# Arduino_Mini.net
KiCad netlist of a schematic drawn in EAGLE
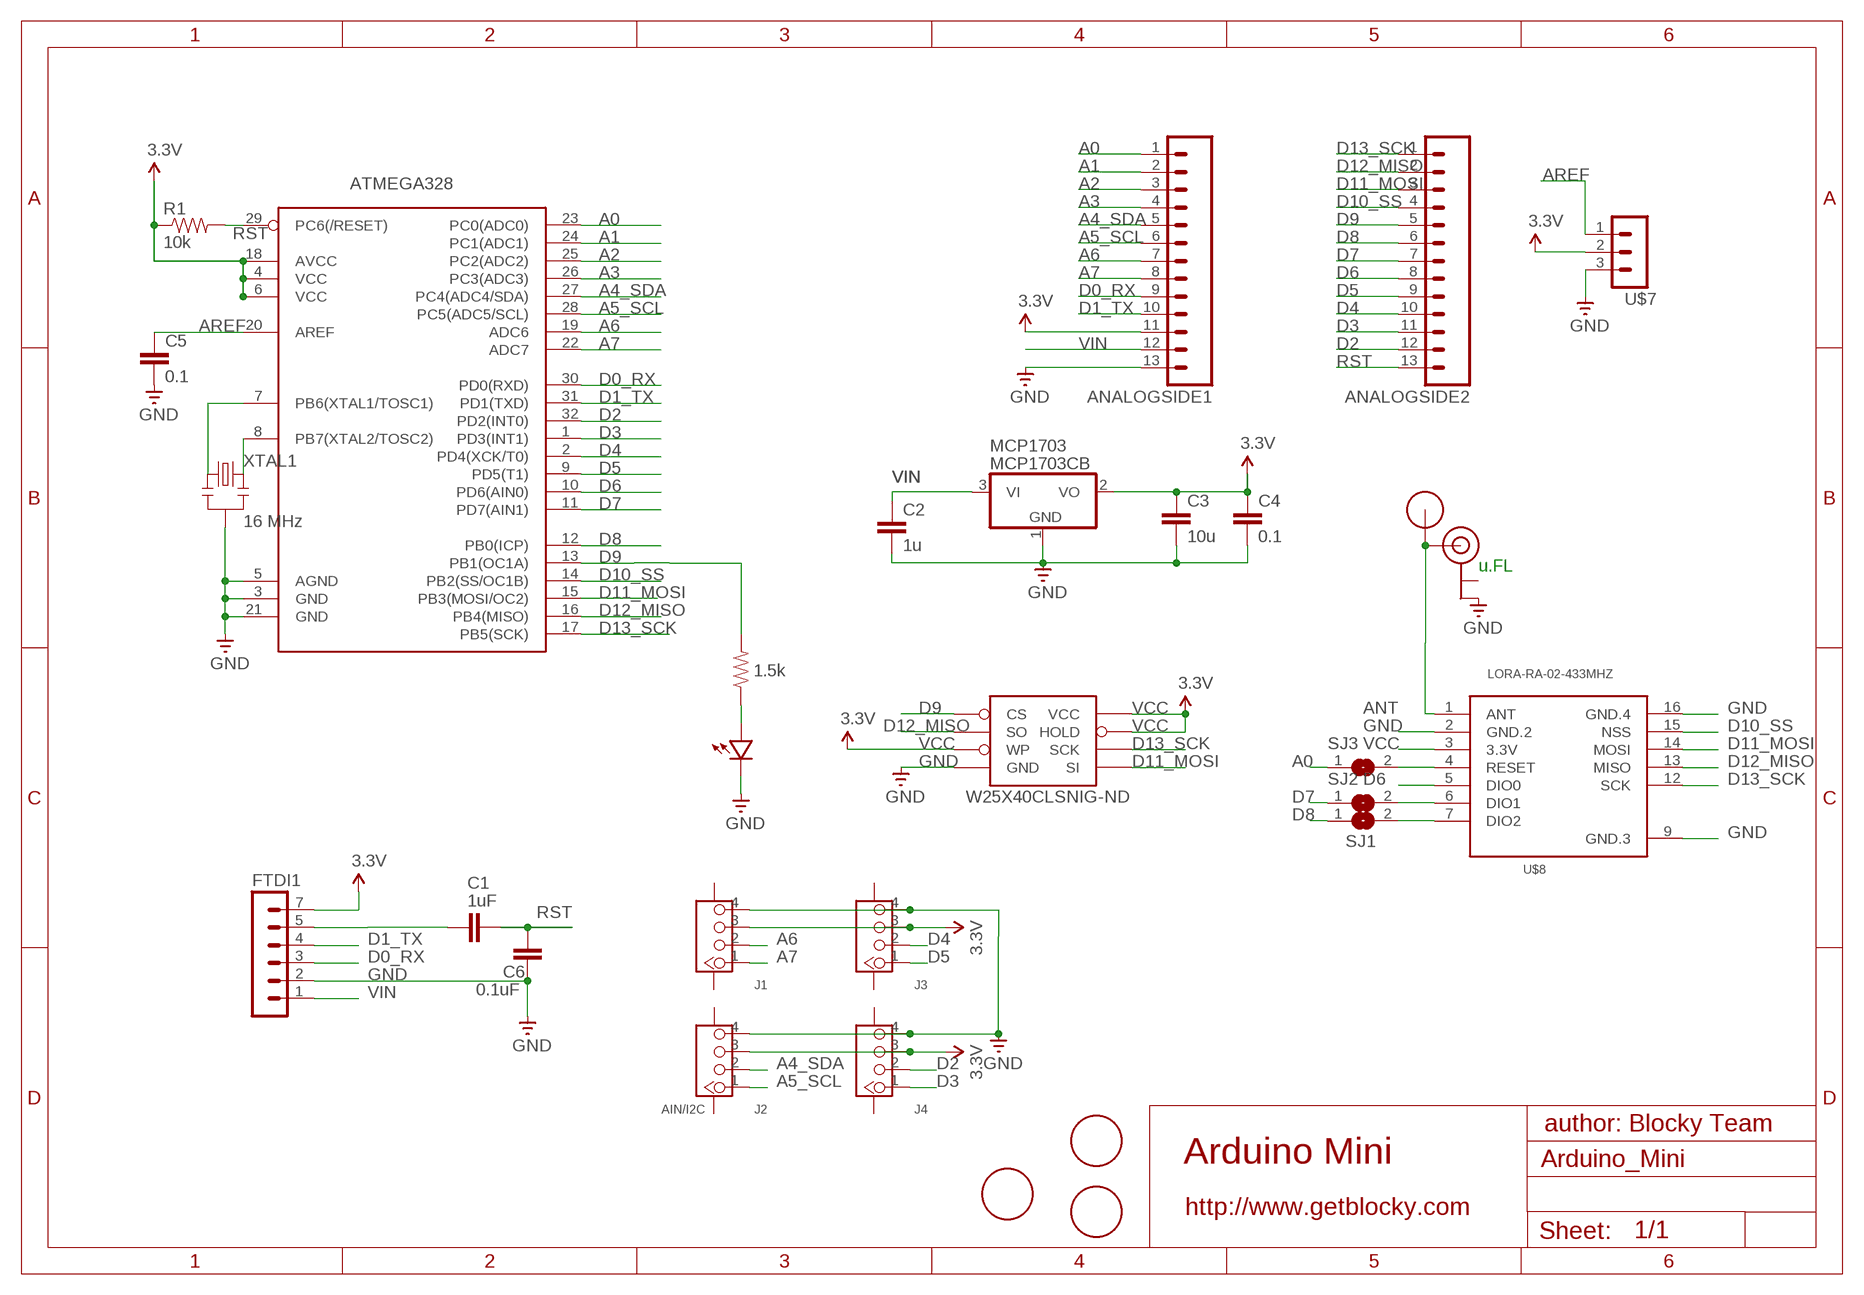
[diagram p0: schematic, sheet 1]

(export (version "E")
  (design (tool "Eeschema 10.0.6"))
  (components
    (comp (ref "ANALOGSIDE1")
      (value "HDR_13PINTHIN_RINGS")
      (footprint "eagle-import:1X13_THINRINGS")
      (libsource (lib "eagle-import") (part "HDR_13PINTHIN_RINGS"))
    )
    (comp (ref "ANALOGSIDE2")
      (value "HDR_13PINTHIN_RINGS")
      (footprint "eagle-import:1X13_THINRINGS")
      (libsource (lib "eagle-import") (part "HDR_13PINTHIN_RINGS"))
    )
    (comp (ref "ATMEGA328")
      (value "ATMega-328")
      (footprint "eagle-import:TQFP32-08")
      (libsource (lib "eagle-import") (part "ATMEGA168/328TQFP32"))
    )
    (comp (ref "C1")
      (value "1uF")
      (footprint "eagle-import:0603-CAP")
      (libsource (lib "eagle-import") (part "CAP0603-CAP"))
    )
    (comp (ref "C2")
      (value "1u")
      (footprint "eagle-import:0603-CAP")
      (libsource (lib "eagle-import") (part "CAP0603-CAP"))
    )
    (comp (ref "C3")
      (value "10u")
      (footprint "eagle-import:0805-CAP")
      (libsource (lib "eagle-import") (part "CAP0805-CAP"))
    )
    (comp (ref "C4")
      (value "0.1")
      (footprint "eagle-import:0603-CAP")
      (libsource (lib "eagle-import") (part "CAP0603-CAP"))
    )
    (comp (ref "C5")
      (value "0.1")
      (footprint "eagle-import:0603-CAP")
      (libsource (lib "eagle-import") (part "CAP0603-CAP"))
    )
    (comp (ref "C6")
      (value "0.1uF")
      (footprint "eagle-import:0603-CAP")
      (libsource (lib "eagle-import") (part "CAP0603-CAP"))
    )
    (comp (ref "FTDI1")
      (value "HDR_6PINTHINRINGS")
      (footprint "eagle-import:1X06_NS_THINRINGS")
      (libsource (lib "eagle-import") (part "HDR_6PINTHINRINGS"))
    )
    (comp (ref "J1")
      (value "4P-SMD-2.0-90D")
      (footprint "eagle-import:HW4-SMD-2.0-90D")
      (libsource (lib "eagle-import") (part "GROVE-CONNECTOR-SMD-90D(4+2P-2.0)"))
    )
    (comp (ref "J2")
      (value "AIN/I2C")
      (footprint "eagle-import:HW4-SMD-2.0-90D")
      (libsource (lib "eagle-import") (part "GROVE-CONNECTOR-SMD-90D(4+2P-2.0)"))
    )
    (comp (ref "J3")
      (value "4P-SMD-2.0-90D")
      (footprint "eagle-import:HW4-SMD-2.0-90D")
      (libsource (lib "eagle-import") (part "GROVE-CONNECTOR-SMD-90D(4+2P-2.0)"))
    )
    (comp (ref "J4")
      (value "4P-SMD-2.0-90D")
      (footprint "eagle-import:HW4-SMD-2.0-90D")
      (libsource (lib "eagle-import") (part "GROVE-CONNECTOR-SMD-90D(4+2P-2.0)"))
    )
    (comp (ref "LED")
      (value "LED0603")
      (footprint "eagle-import:0603-LED")
      (libsource (lib "eagle-import") (part "LED0603"))
    )
    (comp (ref "MCP1703")
      (value "MCP1703CB")
      (footprint "eagle-import:SOT23")
      (libsource (lib "eagle-import") (part "MCP1703CB"))
    )
    (comp (ref "R1")
      (value "10k")
      (footprint "eagle-import:0603-RES")
      (libsource (lib "eagle-import") (part "RESISTOR0603-RES"))
    )
    (comp (ref "R2")
      (value "1.5k")
      (footprint "eagle-import:0603-RES")
      (libsource (lib "eagle-import") (part "RESISTOR0603-RES"))
    )
    (comp (ref "SJ1")
      (value "SOLDERJUMPERREFLOW")
      (footprint "eagle-import:SOLDERJUMPER_REFLOW")
      (libsource (lib "eagle-import") (part "SOLDERJUMPERREFLOW"))
    )
    (comp (ref "SJ2")
      (value "SOLDERJUMPERREFLOW")
      (footprint "eagle-import:SOLDERJUMPER_REFLOW")
      (libsource (lib "eagle-import") (part "SOLDERJUMPERREFLOW"))
    )
    (comp (ref "SJ3")
      (value "SOLDERJUMPERREFLOW")
      (footprint "eagle-import:SOLDERJUMPER_REFLOW")
      (libsource (lib "eagle-import") (part "SOLDERJUMPERREFLOW"))
    )
    (comp (ref "U$1")
      (value "RFM12B_ANTENNA\"\"")
      (footprint "eagle-import:RFM12B-ANTENNA")
      (libsource (lib "eagle-import") (part "RFM12B_ANTENNA{dblquote}{dblquote}"))
    )
    (comp (ref "U$2")
      (value "FIDUCIAL1.5MM")
      (footprint "eagle-import:FIDUCIAL_1.5MM")
      (libsource (lib "eagle-import") (part "FIDUCIAL1.5MM"))
    )
    (comp (ref "U$4")
      (value "U.FL")
      (footprint "eagle-import:U.FL")
      (libsource (lib "eagle-import") (part "U.FL"))
    )
    (comp (ref "U$5")
      (value "FIDUCIAL1.5MM")
      (footprint "eagle-import:FIDUCIAL_1.5MM")
      (libsource (lib "eagle-import") (part "FIDUCIAL1.5MM"))
    )
    (comp (ref "U$6")
      (value "FIDUCIAL1.5MM")
      (footprint "eagle-import:FIDUCIAL_1.5MM")
      (libsource (lib "eagle-import") (part "FIDUCIAL1.5MM"))
    )
    (comp (ref "U$7")
      (value "HDR_3PINTHINRINGS")
      (footprint "eagle-import:1X03_NS_THINRINGS")
      (libsource (lib "eagle-import") (part "HDR_3PINTHINRINGS"))
    )
    (comp (ref "U$8")
      (value "LORA-RA-02-433MHZ")
      (footprint "eagle-import:LORA-RA2-SMD")
      (libsource (lib "eagle-import") (part "LORA-RA-02-433MHZ"))
    )
    (comp (ref "W25X40CLSNIG-ND")
      (value "AT25F512BJEDEC_3.9MM")
      (footprint "eagle-import:SO08")
      (libsource (lib "eagle-import") (part "AT25F512BJEDEC_3.9MM"))
    )
    (comp (ref "XTAL1")
      (value "16 MHz")
      (footprint "eagle-import:RESONATOR-SMD")
      (libsource (lib "eagle-import") (part "RESONATORSMD"))
    )
  )
  (nets
    (net (code "1") (name "/A0") (class "Default")
      (node (ref "ANALOGSIDE1") (pin "1") (pinfunction "1_1") (pintype "passive"))
      (node (ref "ATMEGA328") (pin "23") (pinfunction "PC0(ADC0)_23") (pintype "bidirectional"))
      (node (ref "SJ3") (pin "1") (pinfunction "1_1") (pintype "passive"))
    )
    (net (code "2") (name "/A1") (class "Default")
      (node (ref "ANALOGSIDE1") (pin "2") (pinfunction "2_2") (pintype "passive"))
      (node (ref "ATMEGA328") (pin "24") (pinfunction "PC1(ADC1)_24") (pintype "bidirectional"))
    )
    (net (code "3") (name "/A2") (class "Default")
      (node (ref "ANALOGSIDE1") (pin "3") (pinfunction "3_3") (pintype "passive"))
      (node (ref "ATMEGA328") (pin "25") (pinfunction "PC2(ADC2)_25") (pintype "bidirectional"))
    )
    (net (code "4") (name "/A3") (class "Default")
      (node (ref "ANALOGSIDE1") (pin "4") (pinfunction "4_4") (pintype "passive"))
      (node (ref "ATMEGA328") (pin "26") (pinfunction "PC3(ADC3)_26") (pintype "bidirectional"))
    )
    (net (code "5") (name "/A4_SDA") (class "Default")
      (node (ref "ANALOGSIDE1") (pin "5") (pinfunction "5_5") (pintype "passive"))
      (node (ref "ATMEGA328") (pin "27") (pinfunction "PC4(ADC4/SDA)_27") (pintype "bidirectional"))
      (node (ref "J2") (pin "2") (pinfunction "2_2") (pintype "bidirectional"))
    )
    (net (code "6") (name "/A5_SCL") (class "Default")
      (node (ref "ANALOGSIDE1") (pin "6") (pinfunction "6_6") (pintype "passive"))
      (node (ref "ATMEGA328") (pin "28") (pinfunction "PC5(ADC5/SCL)_28") (pintype "bidirectional"))
      (node (ref "J2") (pin "1") (pinfunction "1_1") (pintype "bidirectional"))
    )
    (net (code "7") (name "/A6") (class "Default")
      (node (ref "ANALOGSIDE1") (pin "7") (pinfunction "7_7") (pintype "passive"))
      (node (ref "ATMEGA328") (pin "19") (pinfunction "ADC6_19") (pintype "bidirectional"))
      (node (ref "J1") (pin "2") (pinfunction "2_2") (pintype "bidirectional"))
    )
    (net (code "8") (name "/A7") (class "Default")
      (node (ref "ANALOGSIDE1") (pin "8") (pinfunction "8_8") (pintype "passive"))
      (node (ref "ATMEGA328") (pin "22") (pinfunction "ADC7_22") (pintype "bidirectional"))
      (node (ref "J1") (pin "1") (pinfunction "1_1") (pintype "bidirectional"))
    )
    (net (code "9") (name "/ANT") (class "Default")
      (node (ref "U$1") (pin "P$1") (pinfunction "1_P$1") (pintype "bidirectional"))
      (node (ref "U$4") (pin "SIGNAL") (pinfunction "SIGNAL_SIGNAL") (pintype "bidirectional"))
      (node (ref "U$8") (pin "1") (pinfunction "ANT_1") (pintype "bidirectional"))
    )
    (net (code "10") (name "/AREF") (class "Default")
      (node (ref "ATMEGA328") (pin "20") (pinfunction "AREF_20") (pintype "bidirectional"))
      (node (ref "C5") (pin "1") (pinfunction "1_1") (pintype "passive"))
      (node (ref "U$7") (pin "1") (pinfunction "1_1") (pintype "passive"))
    )
    (net (code "11") (name "/D0_RX") (class "Default")
      (node (ref "ANALOGSIDE1") (pin "9") (pinfunction "9_9") (pintype "passive"))
      (node (ref "ATMEGA328") (pin "30") (pinfunction "PD0(RXD)_30") (pintype "bidirectional"))
      (node (ref "FTDI1") (pin "3") (pinfunction "3_3") (pintype "passive"))
    )
    (net (code "12") (name "/D1_TX") (class "Default")
      (node (ref "ANALOGSIDE1") (pin "10") (pinfunction "10_10") (pintype "passive"))
      (node (ref "ATMEGA328") (pin "31") (pinfunction "PD1(TXD)_31") (pintype "bidirectional"))
      (node (ref "FTDI1") (pin "4") (pinfunction "4_4") (pintype "passive"))
    )
    (net (code "13") (name "/D2") (class "Default")
      (node (ref "ANALOGSIDE2") (pin "12") (pinfunction "12_12") (pintype "passive"))
      (node (ref "ATMEGA328") (pin "32") (pinfunction "PD2(INT0)_32") (pintype "bidirectional"))
      (node (ref "J4") (pin "2") (pinfunction "2_2") (pintype "bidirectional"))
    )
    (net (code "14") (name "/D3") (class "Default")
      (node (ref "ANALOGSIDE2") (pin "11") (pinfunction "11_11") (pintype "passive"))
      (node (ref "ATMEGA328") (pin "1") (pinfunction "PD3(INT1)_1") (pintype "bidirectional"))
      (node (ref "J4") (pin "1") (pinfunction "1_1") (pintype "bidirectional"))
    )
    (net (code "15") (name "/D4") (class "Default")
      (node (ref "ANALOGSIDE2") (pin "10") (pinfunction "10_10") (pintype "passive"))
      (node (ref "ATMEGA328") (pin "2") (pinfunction "PD4(XCK/T0)_2") (pintype "bidirectional"))
      (node (ref "J3") (pin "2") (pinfunction "2_2") (pintype "bidirectional"))
    )
    (net (code "16") (name "/D5") (class "Default")
      (node (ref "ANALOGSIDE2") (pin "9") (pinfunction "9_9") (pintype "passive"))
      (node (ref "ATMEGA328") (pin "9") (pinfunction "PD5(T1)_9") (pintype "bidirectional"))
      (node (ref "J3") (pin "1") (pinfunction "1_1") (pintype "bidirectional"))
    )
    (net (code "17") (name "/D6") (class "Default")
      (node (ref "ANALOGSIDE2") (pin "8") (pinfunction "8_8") (pintype "passive"))
      (node (ref "ATMEGA328") (pin "10") (pinfunction "PD6(AIN0)_10") (pintype "bidirectional"))
      (node (ref "U$8") (pin "5") (pinfunction "DIO0_5") (pintype "bidirectional"))
    )
    (net (code "18") (name "/D7") (class "Default")
      (node (ref "ANALOGSIDE2") (pin "7") (pinfunction "7_7") (pintype "passive"))
      (node (ref "ATMEGA328") (pin "11") (pinfunction "PD7(AIN1)_11") (pintype "bidirectional"))
      (node (ref "SJ2") (pin "1") (pinfunction "1_1") (pintype "passive"))
    )
    (net (code "19") (name "/D8") (class "Default")
      (node (ref "ANALOGSIDE2") (pin "6") (pinfunction "6_6") (pintype "passive"))
      (node (ref "ATMEGA328") (pin "12") (pinfunction "PB0(ICP)_12") (pintype "bidirectional"))
      (node (ref "SJ1") (pin "1") (pinfunction "1_1") (pintype "passive"))
    )
    (net (code "20") (name "/D9") (class "Default")
      (node (ref "ANALOGSIDE2") (pin "5") (pinfunction "5_5") (pintype "passive"))
      (node (ref "ATMEGA328") (pin "13") (pinfunction "PB1(OC1A)_13") (pintype "bidirectional"))
      (node (ref "R2") (pin "2") (pinfunction "2_2") (pintype "passive"))
      (node (ref "W25X40CLSNIG-ND") (pin "1_CS") (pinfunction "CS_1_CS") (pintype "bidirectional"))
    )
    (net (code "21") (name "/D10_SS") (class "Default")
      (node (ref "ANALOGSIDE2") (pin "4") (pinfunction "4_4") (pintype "passive"))
      (node (ref "ATMEGA328") (pin "14") (pinfunction "PB2(SS/OC1B)_14") (pintype "bidirectional"))
      (node (ref "U$8") (pin "15") (pinfunction "NSS_15") (pintype "bidirectional"))
    )
    (net (code "22") (name "/D11_MOSI") (class "Default")
      (node (ref "ANALOGSIDE2") (pin "3") (pinfunction "3_3") (pintype "passive"))
      (node (ref "ATMEGA328") (pin "15") (pinfunction "PB3(MOSI/OC2)_15") (pintype "bidirectional"))
      (node (ref "U$8") (pin "14") (pinfunction "MOSI_14") (pintype "bidirectional"))
      (node (ref "W25X40CLSNIG-ND") (pin "5_SI") (pinfunction "SI_5_SI") (pintype "bidirectional"))
    )
    (net (code "23") (name "/D12_MISO") (class "Default")
      (node (ref "ANALOGSIDE2") (pin "2") (pinfunction "2_2") (pintype "passive"))
      (node (ref "ATMEGA328") (pin "16") (pinfunction "PB4(MISO)_16") (pintype "bidirectional"))
      (node (ref "U$8") (pin "13") (pinfunction "MISO_13") (pintype "bidirectional"))
      (node (ref "W25X40CLSNIG-ND") (pin "2_SO") (pinfunction "SO_2_SO") (pintype "bidirectional"))
    )
    (net (code "24") (name "/D13_SCK") (class "Default")
      (node (ref "ANALOGSIDE2") (pin "1") (pinfunction "1_1") (pintype "passive"))
      (node (ref "ATMEGA328") (pin "17") (pinfunction "PB5(SCK)_17") (pintype "bidirectional"))
      (node (ref "U$8") (pin "12") (pinfunction "SCK_12") (pintype "bidirectional"))
      (node (ref "W25X40CLSNIG-ND") (pin "6_SCK") (pinfunction "SCK_6_SCK") (pintype "bidirectional"))
    )
    (net (code "25") (name "/RST") (class "Default")
      (node (ref "ANALOGSIDE2") (pin "13") (pinfunction "13_13") (pintype "passive"))
      (node (ref "ATMEGA328") (pin "29") (pinfunction "PC6(/RESET)_29") (pintype "bidirectional"))
      (node (ref "C1") (pin "1") (pinfunction "1_1") (pintype "passive"))
      (node (ref "C6") (pin "1") (pinfunction "1_1") (pintype "passive"))
      (node (ref "R1") (pin "2") (pinfunction "2_2") (pintype "passive"))
    )
    (net (code "26") (name "/VIN") (class "Default")
      (node (ref "ANALOGSIDE1") (pin "12") (pinfunction "12_12") (pintype "passive"))
      (node (ref "C2") (pin "1") (pinfunction "1_1") (pintype "passive"))
      (node (ref "FTDI1") (pin "1") (pinfunction "1_1") (pintype "passive"))
      (node (ref "MCP1703") (pin "3") (pinfunction "VI_3") (pintype "input"))
    )
    (net (code "27") (name "3.3V") (class "Default")
      (node (ref "ANALOGSIDE1") (pin "11") (pinfunction "11_11") (pintype "passive"))
      (node (ref "ATMEGA328") (pin "18") (pinfunction "AVCC_18") (pintype "bidirectional"))
      (node (ref "ATMEGA328") (pin "4") (pinfunction "VCC_4") (pintype "bidirectional"))
      (node (ref "ATMEGA328") (pin "6") (pinfunction "VCC_6") (pintype "bidirectional"))
      (node (ref "C3") (pin "1") (pinfunction "1_1") (pintype "passive"))
      (node (ref "C4") (pin "1") (pinfunction "1_1") (pintype "passive"))
      (node (ref "FTDI1") (pin "7") (pinfunction "6_7") (pintype "passive"))
      (node (ref "J1") (pin "3") (pinfunction "3_3") (pintype "bidirectional"))
      (node (ref "J2") (pin "3") (pinfunction "3_3") (pintype "bidirectional"))
      (node (ref "J3") (pin "3") (pinfunction "3_3") (pintype "bidirectional"))
      (node (ref "J4") (pin "3") (pinfunction "3_3") (pintype "bidirectional"))
      (node (ref "MCP1703") (pin "2") (pinfunction "VO_2") (pintype "passive"))
      (node (ref "R1") (pin "1") (pinfunction "1_1") (pintype "passive"))
      (node (ref "U$7") (pin "2") (pinfunction "2_2") (pintype "passive"))
      (node (ref "U$8") (pin "3") (pinfunction "3.3V_3") (pintype "power_in"))
      (node (ref "W25X40CLSNIG-ND") (pin "3_WP") (pinfunction "WP_3_WP") (pintype "bidirectional"))
      (node (ref "W25X40CLSNIG-ND") (pin "7_HOLD") (pinfunction "HOLD_7_HOLD") (pintype "bidirectional"))
      (node (ref "W25X40CLSNIG-ND") (pin "8_VCC") (pinfunction "VCC_8_VCC") (pintype "bidirectional"))
    )
    (net (code "28") (name "GND") (class "Default")
      (node (ref "ANALOGSIDE1") (pin "13") (pinfunction "13_13") (pintype "passive"))
      (node (ref "ATMEGA328") (pin "21") (pinfunction "GND_21") (pintype "bidirectional"))
      (node (ref "ATMEGA328") (pin "3") (pinfunction "GND_3") (pintype "bidirectional"))
      (node (ref "ATMEGA328") (pin "5") (pinfunction "AGND_5") (pintype "bidirectional"))
      (node (ref "C2") (pin "2") (pinfunction "2_2") (pintype "passive"))
      (node (ref "C3") (pin "2") (pinfunction "2_2") (pintype "passive"))
      (node (ref "C4") (pin "2") (pinfunction "2_2") (pintype "passive"))
      (node (ref "C5") (pin "2") (pinfunction "2_2") (pintype "passive"))
      (node (ref "C6") (pin "2") (pinfunction "2_2") (pintype "passive"))
      (node (ref "FTDI1") (pin "2") (pinfunction "2_2") (pintype "passive"))
      (node (ref "J1") (pin "4") (pinfunction "4_4") (pintype "bidirectional"))
      (node (ref "J2") (pin "4") (pinfunction "4_4") (pintype "bidirectional"))
      (node (ref "J3") (pin "4") (pinfunction "4_4") (pintype "bidirectional"))
      (node (ref "J4") (pin "4") (pinfunction "4_4") (pintype "bidirectional"))
      (node (ref "LED") (pin "MINUS") (pinfunction "MINUS_MINUS") (pintype "passive"))
      (node (ref "MCP1703") (pin "1") (pinfunction "GND_1") (pintype "passive"))
      (node (ref "U$4") (pin "GND2") (pinfunction "GND_GND2") (pintype "bidirectional"))
      (node (ref "U$7") (pin "3") (pinfunction "3_3") (pintype "passive"))
      (node (ref "U$8") (pin "16") (pinfunction "GND.4_16") (pintype "power_in"))
      (node (ref "U$8") (pin "2") (pinfunction "GND.2_2") (pintype "power_in"))
      (node (ref "U$8") (pin "9") (pinfunction "GND.3_9") (pintype "power_in"))
      (node (ref "W25X40CLSNIG-ND") (pin "4_GND") (pinfunction "GND_4_GND") (pintype "bidirectional"))
      (node (ref "XTAL1") (pin "2") (pinfunction "2_2") (pintype "passive"))
    )
    (net (code "29") (name "Net-(ATMEGA328-PB6(XTAL1{slash}TOSC1))") (class "Default")
      (node (ref "ATMEGA328") (pin "7") (pinfunction "PB6(XTAL1/TOSC1)_7") (pintype "bidirectional"))
      (node (ref "XTAL1") (pin "1") (pinfunction "1_1") (pintype "passive"))
    )
    (net (code "30") (name "Net-(ATMEGA328-PB7(XTAL2{slash}TOSC2))") (class "Default")
      (node (ref "ATMEGA328") (pin "8") (pinfunction "PB7(XTAL2/TOSC2)_8") (pintype "bidirectional"))
      (node (ref "XTAL1") (pin "3") (pinfunction "3_3") (pintype "passive"))
    )
    (net (code "31") (name "Net-(C1-Pad2)") (class "Default")
      (node (ref "C1") (pin "2") (pinfunction "2_2") (pintype "passive"))
      (node (ref "FTDI1") (pin "5") (pinfunction "5_5") (pintype "passive"))
    )
    (net (code "32") (name "Net-(LED-PadPLUS)") (class "Default")
      (node (ref "LED") (pin "PLUS") (pinfunction "PLUS_PLUS") (pintype "passive"))
      (node (ref "R2") (pin "1") (pinfunction "1_1") (pintype "passive"))
    )
    (net (code "33") (name "Net-(U$8-DIO1)") (class "Default")
      (node (ref "SJ2") (pin "2") (pinfunction "2_2") (pintype "passive"))
      (node (ref "U$8") (pin "6") (pinfunction "DIO1_6") (pintype "bidirectional"))
    )
    (net (code "34") (name "Net-(U$8-DIO2)") (class "Default")
      (node (ref "SJ1") (pin "2") (pinfunction "2_2") (pintype "passive"))
      (node (ref "U$8") (pin "7") (pinfunction "DIO2_7") (pintype "bidirectional"))
    )
    (net (code "35") (name "Net-(U$8-RESET)") (class "Default")
      (node (ref "SJ3") (pin "2") (pinfunction "2_2") (pintype "passive"))
      (node (ref "U$8") (pin "4") (pinfunction "RESET_4") (pintype "bidirectional"))
    )
    (net (code "36") (name "unconnected-(J1-PadSS1)") (class "Default")
      (node (ref "J1") (pin "SS1") (pinfunction "SS1_SS1") (pintype "bidirectional"))
    )
    (net (code "37") (name "unconnected-(J1-PadSS2)") (class "Default")
      (node (ref "J1") (pin "SS2") (pinfunction "SS2_SS2") (pintype "bidirectional"))
    )
    (net (code "38") (name "unconnected-(J2-PadSS1)") (class "Default")
      (node (ref "J2") (pin "SS1") (pinfunction "SS1_SS1") (pintype "bidirectional"))
    )
    (net (code "39") (name "unconnected-(J2-PadSS2)") (class "Default")
      (node (ref "J2") (pin "SS2") (pinfunction "SS2_SS2") (pintype "bidirectional"))
    )
    (net (code "40") (name "unconnected-(J3-PadSS1)") (class "Default")
      (node (ref "J3") (pin "SS1") (pinfunction "SS1_SS1") (pintype "bidirectional"))
    )
    (net (code "41") (name "unconnected-(J3-PadSS2)") (class "Default")
      (node (ref "J3") (pin "SS2") (pinfunction "SS2_SS2") (pintype "bidirectional"))
    )
    (net (code "42") (name "unconnected-(J4-PadSS1)") (class "Default")
      (node (ref "J4") (pin "SS1") (pinfunction "SS1_SS1") (pintype "bidirectional"))
    )
    (net (code "43") (name "unconnected-(J4-PadSS2)") (class "Default")
      (node (ref "J4") (pin "SS2") (pinfunction "SS2_SS2") (pintype "bidirectional"))
    )
    (net (code "44") (name "unconnected-(U$2-FIDUCIAL-PadP$1)") (class "Default")
      (node (ref "U$2") (pin "P$1") (pinfunction "FIDUCIAL_P$1") (pintype "bidirectional"))
    )
    (net (code "45") (name "unconnected-(U$4-GND-PadGND1)") (class "Default")
      (node (ref "U$4") (pin "GND1") (pinfunction "GND_GND1") (pintype "bidirectional"))
    )
    (net (code "46") (name "unconnected-(U$5-FIDUCIAL-PadP$1)") (class "Default")
      (node (ref "U$5") (pin "P$1") (pinfunction "FIDUCIAL_P$1") (pintype "bidirectional"))
    )
    (net (code "47") (name "unconnected-(U$6-FIDUCIAL-PadP$1)") (class "Default")
      (node (ref "U$6") (pin "P$1") (pinfunction "FIDUCIAL_P$1") (pintype "bidirectional"))
    )
  )
)
